# tractor_v2.net
KiCad netlist of a schematic drawn in EAGLE
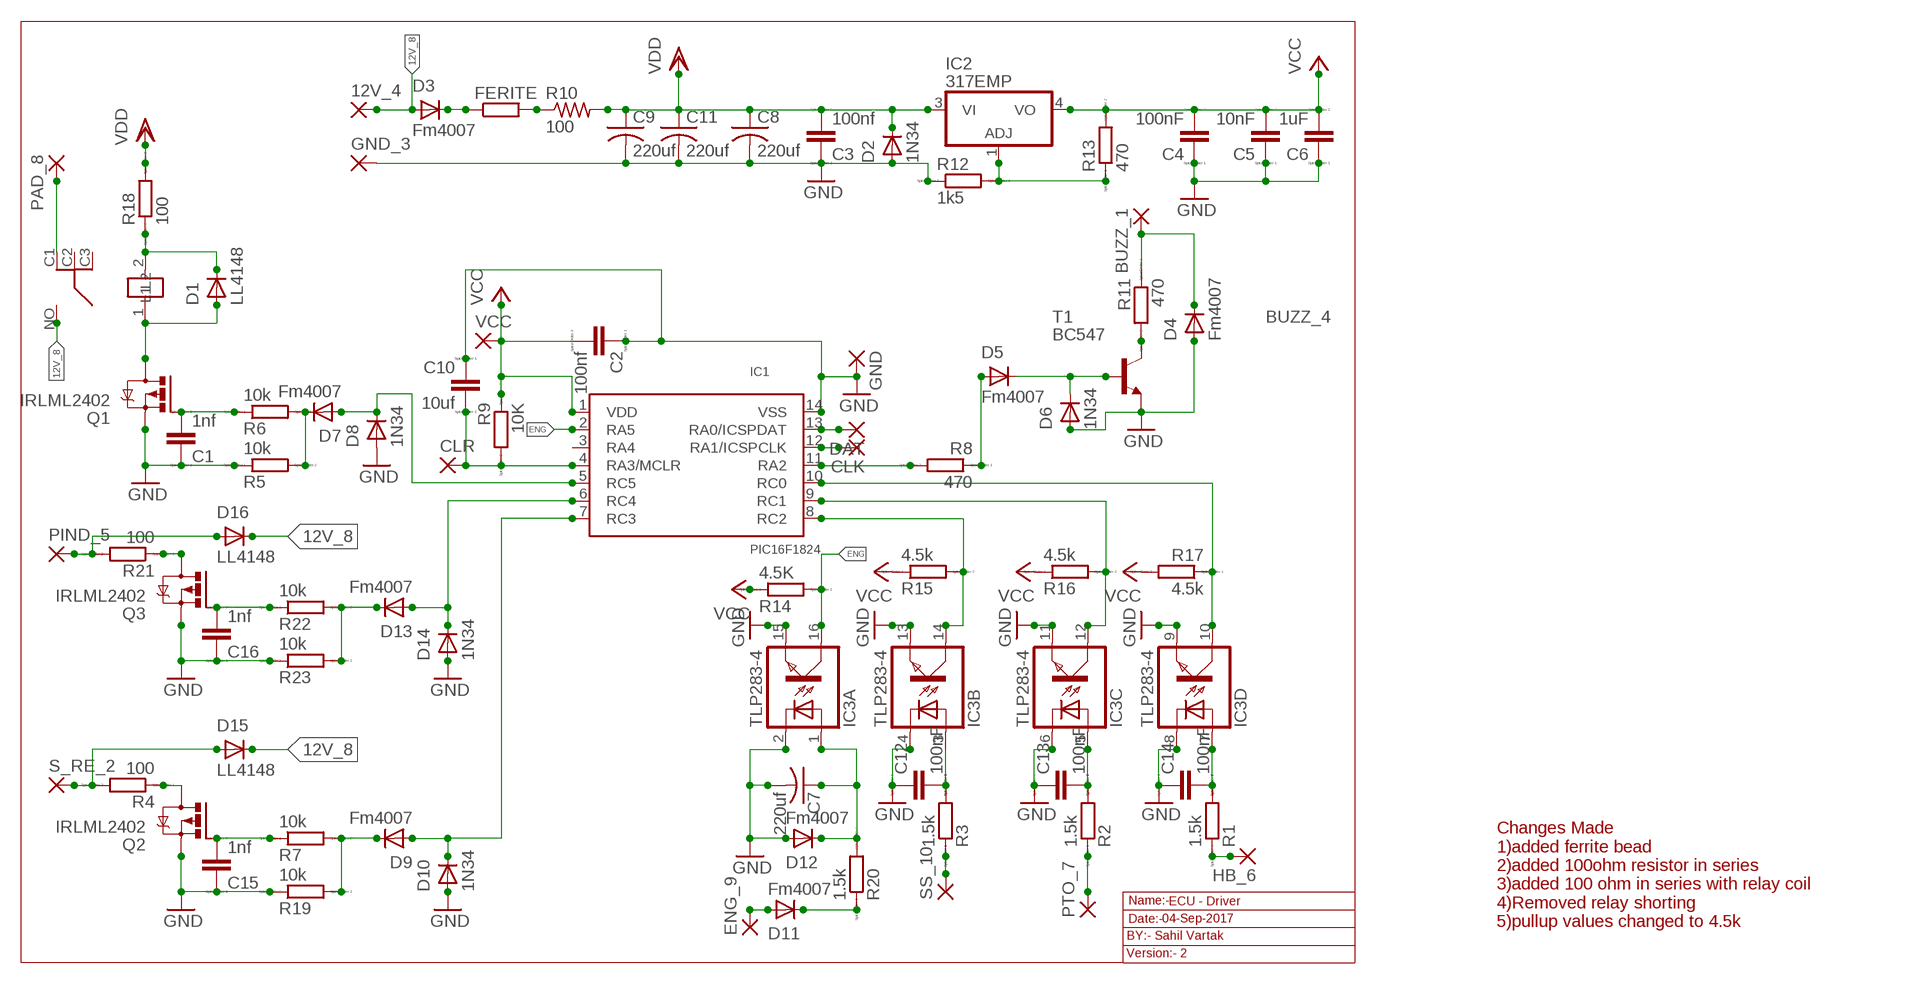
[diagram p0: schematic, sheet 1]

(export (version "E")
  (design (tool "Eeschema 10.0.6"))
  (components
    (comp (ref "12V_4")
      (value "2,54/1,1")
      (footprint "eagle-import:2,54_1,1")
      (libsource (lib "eagle-import") (part "2,54/1,1"))
    )
    (comp (ref "BUZZ_1")
      (value "2,54/1,1")
      (footprint "eagle-import:2,54_1,1")
      (libsource (lib "eagle-import") (part "2,54/1,1"))
    )
    (comp (ref "C1")
      (value "1nf")
      (footprint "eagle-import:C0603")
      (libsource (lib "eagle-import") (part "CC0603"))
    )
    (comp (ref "C2")
      (value "100nf")
      (footprint "eagle-import:C0603")
      (libsource (lib "eagle-import") (part "CC0603"))
    )
    (comp (ref "C3")
      (value "100nf")
      (footprint "eagle-import:C0603")
      (libsource (lib "eagle-import") (part "CC0603"))
    )
    (comp (ref "C4")
      (value "100nF")
      (footprint "eagle-import:C0603")
      (libsource (lib "eagle-import") (part "CC0603"))
    )
    (comp (ref "C5")
      (value "10nF")
      (footprint "eagle-import:C0603")
      (libsource (lib "eagle-import") (part "CC0603"))
    )
    (comp (ref "C6")
      (value "1uF")
      (footprint "eagle-import:C0603")
      (libsource (lib "eagle-import") (part "CC0603"))
    )
    (comp (ref "C7")
      (value "220uf")
      (footprint "eagle-import:C025-025X050")
      (libsource (lib "eagle-import") (part "C-US025-025X050"))
    )
    (comp (ref "C8")
      (value "220uf")
      (footprint "eagle-import:C025-025X050")
      (libsource (lib "eagle-import") (part "C-US025-025X050"))
    )
    (comp (ref "C9")
      (value "220uf")
      (footprint "eagle-import:C025-025X050")
      (libsource (lib "eagle-import") (part "C-US025-025X050"))
    )
    (comp (ref "C10")
      (value "10uf")
      (footprint "eagle-import:C0603")
      (libsource (lib "eagle-import") (part "CC0603"))
    )
    (comp (ref "C11")
      (value "220uf")
      (footprint "eagle-import:C025-025X050")
      (libsource (lib "eagle-import") (part "C-US025-025X050"))
    )
    (comp (ref "C12")
      (value "100nF")
      (footprint "eagle-import:C0603")
      (libsource (lib "eagle-import") (part "CC0603"))
    )
    (comp (ref "C13")
      (value "100nF")
      (footprint "eagle-import:C0603")
      (libsource (lib "eagle-import") (part "CC0603"))
    )
    (comp (ref "C14")
      (value "100nF")
      (footprint "eagle-import:C0603")
      (libsource (lib "eagle-import") (part "CC0603"))
    )
    (comp (ref "C15")
      (value "1nf")
      (footprint "eagle-import:C0603")
      (libsource (lib "eagle-import") (part "CC0603"))
    )
    (comp (ref "C16")
      (value "1nf")
      (footprint "eagle-import:C0603")
      (libsource (lib "eagle-import") (part "CC0603"))
    )
    (comp (ref "CLK")
      (value "1,6/0,8")
      (footprint "eagle-import:1,6_0,8")
      (libsource (lib "eagle-import") (part "1,6/0,8"))
    )
    (comp (ref "CLR")
      (value "1,6/0,8")
      (footprint "eagle-import:1,6_0,8")
      (libsource (lib "eagle-import") (part "1,6/0,8"))
    )
    (comp (ref "D1")
      (value "LL4148")
      (footprint "eagle-import:SMA-DO214AC")
      (libsource (lib "eagle-import") (part "GF1"))
    )
    (comp (ref "D2")
      (value "1N34")
      (footprint "eagle-import:SMA-DO214AC")
      (libsource (lib "eagle-import") (part "GF1"))
    )
    (comp (ref "D3")
      (value "Fm4007")
      (footprint "eagle-import:SMA-DO214AC")
      (libsource (lib "eagle-import") (part "GF1"))
    )
    (comp (ref "D4")
      (value "Fm4007")
      (footprint "eagle-import:SMA-DO214AC")
      (libsource (lib "eagle-import") (part "GF1"))
    )
    (comp (ref "D5")
      (value "Fm4007")
      (footprint "eagle-import:SMA-DO214AC")
      (libsource (lib "eagle-import") (part "GF1"))
    )
    (comp (ref "D6")
      (value "1N34")
      (footprint "eagle-import:SMA-DO214AC")
      (libsource (lib "eagle-import") (part "GF1"))
    )
    (comp (ref "D7")
      (value "Fm4007")
      (footprint "eagle-import:SMA-DO214AC")
      (libsource (lib "eagle-import") (part "GF1"))
    )
    (comp (ref "D8")
      (value "1N34")
      (footprint "eagle-import:SMA-DO214AC")
      (libsource (lib "eagle-import") (part "GF1"))
    )
    (comp (ref "D9")
      (value "Fm4007")
      (footprint "eagle-import:SMA-DO214AC")
      (libsource (lib "eagle-import") (part "GF1"))
    )
    (comp (ref "D10")
      (value "1N34")
      (footprint "eagle-import:SMA-DO214AC")
      (libsource (lib "eagle-import") (part "GF1"))
    )
    (comp (ref "D11")
      (value "Fm4007")
      (footprint "eagle-import:SMA-DO214AC")
      (libsource (lib "eagle-import") (part "GF1"))
    )
    (comp (ref "D12")
      (value "Fm4007")
      (footprint "eagle-import:SMA-DO214AC")
      (libsource (lib "eagle-import") (part "GF1"))
    )
    (comp (ref "D13")
      (value "Fm4007")
      (footprint "eagle-import:SMA-DO214AC")
      (libsource (lib "eagle-import") (part "GF1"))
    )
    (comp (ref "D14")
      (value "1N34")
      (footprint "eagle-import:SMA-DO214AC")
      (libsource (lib "eagle-import") (part "GF1"))
    )
    (comp (ref "D15")
      (value "LL4148")
      (footprint "eagle-import:SMA-DO214AC")
      (libsource (lib "eagle-import") (part "GF1"))
    )
    (comp (ref "D16")
      (value "LL4148")
      (footprint "eagle-import:SMA-DO214AC")
      (libsource (lib "eagle-import") (part "GF1"))
    )
    (comp (ref "DAT")
      (value "1,6/0,8")
      (footprint "eagle-import:1,6_0,8")
      (libsource (lib "eagle-import") (part "1,6/0,8"))
    )
    (comp (ref "ENG_9")
      (value "2,54/1,1")
      (footprint "eagle-import:2,54_1,1")
      (libsource (lib "eagle-import") (part "2,54/1,1"))
    )
    (comp (ref "FERITE")
      (value "R-EU_R0603")
      (footprint "eagle-import:R0603")
      (libsource (lib "eagle-import") (part "R-EU_R0603"))
    )
    (comp (ref "GND")
      (value "1,6/0,8")
      (footprint "eagle-import:1,6_0,8")
      (libsource (lib "eagle-import") (part "1,6/0,8"))
    )
    (comp (ref "GND_3")
      (value "2,54/1,1")
      (footprint "eagle-import:2,54_1,1")
      (libsource (lib "eagle-import") (part "2,54/1,1"))
    )
    (comp (ref "HB_6")
      (value "2,54/1,1")
      (footprint "eagle-import:2,54_1,1")
      (libsource (lib "eagle-import") (part "2,54/1,1"))
    )
    (comp (ref "IC1")
      (value "PIC16F1824")
      (footprint "eagle-import:SO-14")
      (libsource (lib "eagle-import") (part "PIC16F1824"))
    )
    (comp (ref "IC2")
      (value "317EMP")
      (footprint "eagle-import:SOT223")
      (libsource (lib "eagle-import") (part "317EMP"))
    )
    (comp (ref "IC3")
      (value "TLP283-4")
      (footprint "eagle-import:MINI-FLAT-16")
      (libsource (lib "eagle-import") (part "TLP283-4"))
    )
    (comp (ref "K2")
      (value "RL703")
      (footprint "eagle-import:RL703")
      (libsource (lib "eagle-import") (part "RL703"))
    )
    (comp (ref "PAD_8")
      (value "2,54/1,1")
      (footprint "eagle-import:2,54_1,1")
      (libsource (lib "eagle-import") (part "2,54/1,1"))
    )
    (comp (ref "PIND_5")
      (value "2,54/1,1")
      (footprint "eagle-import:2,54_1,1")
      (libsource (lib "eagle-import") (part "2,54/1,1"))
    )
    (comp (ref "PTO_7")
      (value "2,54/1,1")
      (footprint "eagle-import:2,54_1,1")
      (libsource (lib "eagle-import") (part "2,54/1,1"))
    )
    (comp (ref "Q1")
      (value "IRLML2402")
      (footprint "eagle-import:MICRO3")
      (libsource (lib "eagle-import") (part "IRLML5203"))
    )
    (comp (ref "Q2")
      (value "IRLML2402")
      (footprint "eagle-import:MICRO3")
      (libsource (lib "eagle-import") (part "IRLML5203"))
    )
    (comp (ref "Q3")
      (value "IRLML2402")
      (footprint "eagle-import:MICRO3")
      (libsource (lib "eagle-import") (part "IRLML5203"))
    )
    (comp (ref "R1")
      (value "1.5k")
      (footprint "eagle-import:R0603")
      (libsource (lib "eagle-import") (part "RR0603"))
    )
    (comp (ref "R2")
      (value "1.5k")
      (footprint "eagle-import:R0603")
      (libsource (lib "eagle-import") (part "RR0603"))
    )
    (comp (ref "R3")
      (value "1.5k")
      (footprint "eagle-import:R0603")
      (libsource (lib "eagle-import") (part "RR0603"))
    )
    (comp (ref "R4")
      (value "100")
      (footprint "eagle-import:R0603")
      (libsource (lib "eagle-import") (part "RR0603"))
    )
    (comp (ref "R5")
      (value "10k")
      (footprint "eagle-import:R0603")
      (libsource (lib "eagle-import") (part "RR0603"))
    )
    (comp (ref "R6")
      (value "10k")
      (footprint "eagle-import:R0603")
      (libsource (lib "eagle-import") (part "RR0603"))
    )
    (comp (ref "R7")
      (value "10k")
      (footprint "eagle-import:R0603")
      (libsource (lib "eagle-import") (part "RR0603"))
    )
    (comp (ref "R8")
      (value "470")
      (footprint "eagle-import:R0603")
      (libsource (lib "eagle-import") (part "RR0603"))
    )
    (comp (ref "R9")
      (value "10K")
      (footprint "eagle-import:R0603")
      (libsource (lib "eagle-import") (part "RR0603"))
    )
    (comp (ref "R10")
      (value "100")
      (footprint "eagle-import:WSC2515")
      (libsource (lib "eagle-import") (part "R-US_WSC2515"))
    )
    (comp (ref "R11")
      (value "470")
      (footprint "eagle-import:R0603")
      (libsource (lib "eagle-import") (part "RR0603"))
    )
    (comp (ref "R12")
      (value "1k5")
      (footprint "eagle-import:R0603")
      (libsource (lib "eagle-import") (part "RR0603"))
    )
    (comp (ref "R13")
      (value "470")
      (footprint "eagle-import:R0603")
      (libsource (lib "eagle-import") (part "RR0603"))
    )
    (comp (ref "R14")
      (value "4.5K")
      (footprint "eagle-import:R0603")
      (libsource (lib "eagle-import") (part "RR0603"))
    )
    (comp (ref "R15")
      (value "4.5k")
      (footprint "eagle-import:R0603")
      (libsource (lib "eagle-import") (part "RR0603"))
    )
    (comp (ref "R16")
      (value "4.5k")
      (footprint "eagle-import:R0603")
      (libsource (lib "eagle-import") (part "RR0603"))
    )
    (comp (ref "R17")
      (value "4.5k")
      (footprint "eagle-import:R0603")
      (libsource (lib "eagle-import") (part "RR0603"))
    )
    (comp (ref "R18")
      (value "100")
      (footprint "eagle-import:R0603")
      (libsource (lib "eagle-import") (part "RR0603"))
    )
    (comp (ref "R19")
      (value "10k")
      (footprint "eagle-import:R0603")
      (libsource (lib "eagle-import") (part "RR0603"))
    )
    (comp (ref "R20")
      (value "1.5k")
      (footprint "eagle-import:R0603")
      (libsource (lib "eagle-import") (part "RR0603"))
    )
    (comp (ref "R21")
      (value "100")
      (footprint "eagle-import:R0603")
      (libsource (lib "eagle-import") (part "RR0603"))
    )
    (comp (ref "R22")
      (value "10k")
      (footprint "eagle-import:R0603")
      (libsource (lib "eagle-import") (part "RR0603"))
    )
    (comp (ref "R23")
      (value "10k")
      (footprint "eagle-import:R0603")
      (libsource (lib "eagle-import") (part "RR0603"))
    )
    (comp (ref "SS_10")
      (value "2,54/1,1")
      (footprint "eagle-import:2,54_1,1")
      (libsource (lib "eagle-import") (part "2,54/1,1"))
    )
    (comp (ref "S_RE_2")
      (value "2,54/1,1")
      (footprint "eagle-import:2,54_1,1")
      (libsource (lib "eagle-import") (part "2,54/1,1"))
    )
    (comp (ref "T1")
      (value "BC547")
      (footprint "eagle-import:TO92")
      (libsource (lib "eagle-import") (part "BC547"))
    )
    (comp (ref "VCC")
      (value "1,6/0,8")
      (footprint "eagle-import:1,6_0,8")
      (libsource (lib "eagle-import") (part "1,6/0,8"))
    )
  )
  (nets
    (net (code "1") (name "/BUZZ_4") (class "Default")
      (node (ref "BUZZ_1") (pin "1") (pinfunction "P_1") (pintype "passive"))
      (node (ref "D4") (pin "K") (pinfunction "C_K") (pintype "passive"))
      (node (ref "R11") (pin "1") (pinfunction "1_1") (pintype "passive"))
    )
    (net (code "2") (name "12V_8") (class "Default")
      (node (ref "12V_4") (pin "1") (pinfunction "P_1") (pintype "passive"))
      (node (ref "D15") (pin "K") (pinfunction "C_K") (pintype "passive"))
      (node (ref "D16") (pin "K") (pinfunction "C_K") (pintype "passive"))
      (node (ref "D3") (pin "A") (pinfunction "A_A") (pintype "passive"))
      (node (ref "K2") (pin "NO") (pinfunction "NO_NO") (pintype "bidirectional"))
    )
    (net (code "3") (name "ENG") (class "Default")
      (node (ref "IC1") (pin "2") (pinfunction "RA5_2") (pintype "bidirectional"))
      (node (ref "IC3") (pin "16") (pinfunction "COL_16") (pintype "passive"))
      (node (ref "R14") (pin "2") (pinfunction "2_2") (pintype "passive"))
    )
    (net (code "4") (name "GND") (class "Default")
      (node (ref "C1") (pin "1") (pinfunction "1_1") (pintype "passive"))
      (node (ref "C10") (pin "1") (pinfunction "1_1") (pintype "passive"))
      (node (ref "C11") (pin "2") (pinfunction "2_2") (pintype "passive"))
      (node (ref "C12") (pin "1") (pinfunction "1_1") (pintype "passive"))
      (node (ref "C13") (pin "1") (pinfunction "1_1") (pintype "passive"))
      (node (ref "C14") (pin "1") (pinfunction "1_1") (pintype "passive"))
      (node (ref "C15") (pin "1") (pinfunction "1_1") (pintype "passive"))
      (node (ref "C16") (pin "1") (pinfunction "1_1") (pintype "passive"))
      (node (ref "C2") (pin "1") (pinfunction "1_1") (pintype "passive"))
      (node (ref "C3") (pin "1") (pinfunction "1_1") (pintype "passive"))
      (node (ref "C4") (pin "1") (pinfunction "1_1") (pintype "passive"))
      (node (ref "C5") (pin "1") (pinfunction "1_1") (pintype "passive"))
      (node (ref "C6") (pin "1") (pinfunction "1_1") (pintype "passive"))
      (node (ref "C7") (pin "2") (pinfunction "2_2") (pintype "passive"))
      (node (ref "C8") (pin "2") (pinfunction "2_2") (pintype "passive"))
      (node (ref "C9") (pin "2") (pinfunction "2_2") (pintype "passive"))
      (node (ref "D10") (pin "A") (pinfunction "A_A") (pintype "passive"))
      (node (ref "D12") (pin "A") (pinfunction "A_A") (pintype "passive"))
      (node (ref "D14") (pin "A") (pinfunction "A_A") (pintype "passive"))
      (node (ref "D2") (pin "A") (pinfunction "A_A") (pintype "passive"))
      (node (ref "D4") (pin "A") (pinfunction "A_A") (pintype "passive"))
      (node (ref "D6") (pin "A") (pinfunction "A_A") (pintype "passive"))
      (node (ref "D8") (pin "A") (pinfunction "A_A") (pintype "passive"))
      (node (ref "GND") (pin "1") (pinfunction "P_1") (pintype "passive"))
      (node (ref "GND_3") (pin "1") (pinfunction "P_1") (pintype "passive"))
      (node (ref "IC1") (pin "14") (pinfunction "VSS_14") (pintype "bidirectional"))
      (node (ref "IC3") (pin "11") (pinfunction "EMIT_11") (pintype "passive"))
      (node (ref "IC3") (pin "13") (pinfunction "EMIT_13") (pintype "passive"))
      (node (ref "IC3") (pin "15") (pinfunction "EMIT_15") (pintype "passive"))
      (node (ref "IC3") (pin "2") (pinfunction "C_2") (pintype "passive"))
      (node (ref "IC3") (pin "4") (pinfunction "C_4") (pintype "passive"))
      (node (ref "IC3") (pin "6") (pinfunction "C_6") (pintype "passive"))
      (node (ref "IC3") (pin "8") (pinfunction "C_8") (pintype "passive"))
      (node (ref "IC3") (pin "9") (pinfunction "EMIT_9") (pintype "passive"))
      (node (ref "Q1") (pin "2") (pinfunction "S_2") (pintype "passive"))
      (node (ref "Q2") (pin "2") (pinfunction "S_2") (pintype "passive"))
      (node (ref "Q3") (pin "2") (pinfunction "S_2") (pintype "passive"))
      (node (ref "R12") (pin "1") (pinfunction "1_1") (pintype "passive"))
      (node (ref "R19") (pin "1") (pinfunction "1_1") (pintype "passive"))
      (node (ref "R23") (pin "1") (pinfunction "1_1") (pintype "passive"))
      (node (ref "R5") (pin "1") (pinfunction "1_1") (pintype "passive"))
      (node (ref "T1") (pin "1") (pinfunction "E_1") (pintype "passive"))
    )
    (net (code "5") (name "Net-(CLK-P)") (class "Default")
      (node (ref "CLK") (pin "1") (pinfunction "P_1") (pintype "passive"))
      (node (ref "IC1") (pin "12") (pinfunction "RA1/ICSPCLK_12") (pintype "bidirectional"))
    )
    (net (code "6") (name "Net-(CLR-P)") (class "Default")
      (node (ref "C10") (pin "2") (pinfunction "2_2") (pintype "passive"))
      (node (ref "CLR") (pin "1") (pinfunction "P_1") (pintype "passive"))
      (node (ref "IC1") (pin "4") (pinfunction "RA3/MCLR_4") (pintype "bidirectional"))
      (node (ref "R9") (pin "2") (pinfunction "2_2") (pintype "passive"))
    )
    (net (code "7") (name "Net-(D1-C)") (class "Default")
      (node (ref "D1") (pin "K") (pinfunction "C_K") (pintype "passive"))
      (node (ref "K2") (pin "2") (pinfunction "L1_2") (pintype "bidirectional"))
      (node (ref "R18") (pin "1") (pinfunction "1_1") (pintype "passive"))
    )
    (net (code "8") (name "Net-(D3-C)") (class "Default")
      (node (ref "D3") (pin "K") (pinfunction "C_K") (pintype "passive"))
      (node (ref "FERITE") (pin "1") (pinfunction "1_1") (pintype "passive"))
    )
    (net (code "9") (name "Net-(D5-C)") (class "Default")
      (node (ref "D5") (pin "K") (pinfunction "C_K") (pintype "passive"))
      (node (ref "D6") (pin "K") (pinfunction "C_K") (pintype "passive"))
      (node (ref "T1") (pin "2") (pinfunction "B_2") (pintype "passive"))
    )
    (net (code "10") (name "Net-(D5-PadA)") (class "Default")
      (node (ref "D5") (pin "A") (pinfunction "A_A") (pintype "passive"))
      (node (ref "R8") (pin "1") (pinfunction "1_1") (pintype "passive"))
    )
    (net (code "11") (name "Net-(D7-C)") (class "Default")
      (node (ref "D7") (pin "K") (pinfunction "C_K") (pintype "passive"))
      (node (ref "R5") (pin "2") (pinfunction "2_2") (pintype "passive"))
      (node (ref "R6") (pin "2") (pinfunction "2_2") (pintype "passive"))
    )
    (net (code "12") (name "Net-(D8-C)") (class "Default")
      (node (ref "D7") (pin "A") (pinfunction "A_A") (pintype "passive"))
      (node (ref "D8") (pin "K") (pinfunction "C_K") (pintype "passive"))
      (node (ref "IC1") (pin "5") (pinfunction "RC5_5") (pintype "bidirectional"))
    )
    (net (code "13") (name "Net-(D9-C)") (class "Default")
      (node (ref "D9") (pin "K") (pinfunction "C_K") (pintype "passive"))
      (node (ref "R19") (pin "2") (pinfunction "2_2") (pintype "passive"))
      (node (ref "R7") (pin "2") (pinfunction "2_2") (pintype "passive"))
    )
    (net (code "14") (name "Net-(D10-C)") (class "Default")
      (node (ref "D10") (pin "K") (pinfunction "C_K") (pintype "passive"))
      (node (ref "D9") (pin "A") (pinfunction "A_A") (pintype "passive"))
      (node (ref "IC1") (pin "7") (pinfunction "RC3_7") (pintype "bidirectional"))
    )
    (net (code "15") (name "Net-(D11-C)") (class "Default")
      (node (ref "D11") (pin "K") (pinfunction "C_K") (pintype "passive"))
      (node (ref "R20") (pin "1") (pinfunction "1_1") (pintype "passive"))
    )
    (net (code "16") (name "Net-(D12-C)") (class "Default")
      (node (ref "C7") (pin "1") (pinfunction "1_1") (pintype "passive"))
      (node (ref "D12") (pin "K") (pinfunction "C_K") (pintype "passive"))
      (node (ref "IC3") (pin "1") (pinfunction "A_1") (pintype "passive"))
      (node (ref "R20") (pin "2") (pinfunction "2_2") (pintype "passive"))
    )
    (net (code "17") (name "Net-(D13-C)") (class "Default")
      (node (ref "D13") (pin "K") (pinfunction "C_K") (pintype "passive"))
      (node (ref "R22") (pin "2") (pinfunction "2_2") (pintype "passive"))
      (node (ref "R23") (pin "2") (pinfunction "2_2") (pintype "passive"))
    )
    (net (code "18") (name "Net-(D14-C)") (class "Default")
      (node (ref "D13") (pin "A") (pinfunction "A_A") (pintype "passive"))
      (node (ref "D14") (pin "K") (pinfunction "C_K") (pintype "passive"))
      (node (ref "IC1") (pin "6") (pinfunction "RC4_6") (pintype "bidirectional"))
    )
    (net (code "19") (name "Net-(DAT-P)") (class "Default")
      (node (ref "DAT") (pin "1") (pinfunction "P_1") (pintype "passive"))
      (node (ref "IC1") (pin "13") (pinfunction "RA0/ICSPDAT_13") (pintype "bidirectional"))
    )
    (net (code "20") (name "Net-(ENG_9-P)") (class "Default")
      (node (ref "D11") (pin "A") (pinfunction "A_A") (pintype "passive"))
      (node (ref "ENG_9") (pin "1") (pinfunction "P_1") (pintype "passive"))
    )
    (net (code "21") (name "Net-(FERITE-Pad2)") (class "Default")
      (node (ref "FERITE") (pin "2") (pinfunction "2_2") (pintype "passive"))
      (node (ref "R10") (pin "1") (pinfunction "1_1") (pintype "passive"))
    )
    (net (code "22") (name "Net-(HB_6-P)") (class "Default")
      (node (ref "HB_6") (pin "1") (pinfunction "P_1") (pintype "passive"))
      (node (ref "R1") (pin "1") (pinfunction "1_1") (pintype "passive"))
    )
    (net (code "23") (name "Net-(IC1-RA2)") (class "Default")
      (node (ref "IC1") (pin "11") (pinfunction "RA2_11") (pintype "bidirectional"))
      (node (ref "R8") (pin "2") (pinfunction "2_2") (pintype "passive"))
    )
    (net (code "24") (name "Net-(IC1-RC0)") (class "Default")
      (node (ref "IC1") (pin "10") (pinfunction "RC0_10") (pintype "bidirectional"))
      (node (ref "IC3") (pin "10") (pinfunction "COL_10") (pintype "passive"))
      (node (ref "R17") (pin "1") (pinfunction "1_1") (pintype "passive"))
    )
    (net (code "25") (name "Net-(IC1-RC1)") (class "Default")
      (node (ref "IC1") (pin "9") (pinfunction "RC1_9") (pintype "bidirectional"))
      (node (ref "IC3") (pin "12") (pinfunction "COL_12") (pintype "passive"))
      (node (ref "R16") (pin "2") (pinfunction "2_2") (pintype "passive"))
    )
    (net (code "26") (name "Net-(IC1-RC2)") (class "Default")
      (node (ref "IC1") (pin "8") (pinfunction "RC2_8") (pintype "bidirectional"))
      (node (ref "IC3") (pin "14") (pinfunction "COL_14") (pintype "passive"))
      (node (ref "R15") (pin "2") (pinfunction "2_2") (pintype "passive"))
    )
    (net (code "27") (name "Net-(IC2-ADJ)") (class "Default")
      (node (ref "IC2") (pin "1") (pinfunction "ADJ_1") (pintype "input"))
      (node (ref "R12") (pin "2") (pinfunction "2_2") (pintype "passive"))
      (node (ref "R13") (pin "1") (pinfunction "1_1") (pintype "passive"))
    )
    (net (code "28") (name "Net-(IC3B-A)") (class "Default")
      (node (ref "C12") (pin "2") (pinfunction "2_2") (pintype "passive"))
      (node (ref "IC3") (pin "3") (pinfunction "A_3") (pintype "passive"))
      (node (ref "R3") (pin "2") (pinfunction "2_2") (pintype "passive"))
    )
    (net (code "29") (name "Net-(IC3C-A)") (class "Default")
      (node (ref "C13") (pin "2") (pinfunction "2_2") (pintype "passive"))
      (node (ref "IC3") (pin "5") (pinfunction "A_5") (pintype "passive"))
      (node (ref "R2") (pin "2") (pinfunction "2_2") (pintype "passive"))
    )
    (net (code "30") (name "Net-(IC3D-A)") (class "Default")
      (node (ref "C14") (pin "2") (pinfunction "2_2") (pintype "passive"))
      (node (ref "IC3") (pin "7") (pinfunction "A_7") (pintype "passive"))
      (node (ref "R1") (pin "2") (pinfunction "2_2") (pintype "passive"))
    )
    (net (code "31") (name "Net-(K2-L2)") (class "Default")
      (node (ref "D1") (pin "A") (pinfunction "A_A") (pintype "passive"))
      (node (ref "K2") (pin "1") (pinfunction "L2_1") (pintype "bidirectional"))
      (node (ref "Q1") (pin "3") (pinfunction "D_3") (pintype "passive"))
    )
    (net (code "32") (name "Net-(PAD_8-P)") (class "Default")
      (node (ref "K2") (pin "C1") (pinfunction "C1_C1") (pintype "bidirectional"))
      (node (ref "PAD_8") (pin "1") (pinfunction "P_1") (pintype "passive"))
    )
    (net (code "33") (name "Net-(PIND_5-P)") (class "Default")
      (node (ref "D16") (pin "A") (pinfunction "A_A") (pintype "passive"))
      (node (ref "PIND_5") (pin "1") (pinfunction "P_1") (pintype "passive"))
      (node (ref "R21") (pin "2") (pinfunction "2_2") (pintype "passive"))
    )
    (net (code "34") (name "Net-(PTO_7-P)") (class "Default")
      (node (ref "PTO_7") (pin "1") (pinfunction "P_1") (pintype "passive"))
      (node (ref "R2") (pin "1") (pinfunction "1_1") (pintype "passive"))
    )
    (net (code "35") (name "Net-(Q1-G)") (class "Default")
      (node (ref "C1") (pin "2") (pinfunction "2_2") (pintype "passive"))
      (node (ref "Q1") (pin "1") (pinfunction "G_1") (pintype "passive"))
      (node (ref "R6") (pin "1") (pinfunction "1_1") (pintype "passive"))
    )
    (net (code "36") (name "Net-(Q2-D)") (class "Default")
      (node (ref "Q2") (pin "3") (pinfunction "D_3") (pintype "passive"))
      (node (ref "R4") (pin "1") (pinfunction "1_1") (pintype "passive"))
    )
    (net (code "37") (name "Net-(Q2-G)") (class "Default")
      (node (ref "C15") (pin "2") (pinfunction "2_2") (pintype "passive"))
      (node (ref "Q2") (pin "1") (pinfunction "G_1") (pintype "passive"))
      (node (ref "R7") (pin "1") (pinfunction "1_1") (pintype "passive"))
    )
    (net (code "38") (name "Net-(Q3-D)") (class "Default")
      (node (ref "Q3") (pin "3") (pinfunction "D_3") (pintype "passive"))
      (node (ref "R21") (pin "1") (pinfunction "1_1") (pintype "passive"))
    )
    (net (code "39") (name "Net-(Q3-G)") (class "Default")
      (node (ref "C16") (pin "2") (pinfunction "2_2") (pintype "passive"))
      (node (ref "Q3") (pin "1") (pinfunction "G_1") (pintype "passive"))
      (node (ref "R22") (pin "1") (pinfunction "1_1") (pintype "passive"))
    )
    (net (code "40") (name "Net-(SS_10-P)") (class "Default")
      (node (ref "R3") (pin "1") (pinfunction "1_1") (pintype "passive"))
      (node (ref "SS_10") (pin "1") (pinfunction "P_1") (pintype "passive"))
    )
    (net (code "41") (name "Net-(S_RE_2-P)") (class "Default")
      (node (ref "D15") (pin "A") (pinfunction "A_A") (pintype "passive"))
      (node (ref "R4") (pin "2") (pinfunction "2_2") (pintype "passive"))
      (node (ref "S_RE_2") (pin "1") (pinfunction "P_1") (pintype "passive"))
    )
    (net (code "42") (name "Net-(T1-C)") (class "Default")
      (node (ref "R11") (pin "2") (pinfunction "2_2") (pintype "passive"))
      (node (ref "T1") (pin "3") (pinfunction "C_3") (pintype "passive"))
    )
    (net (code "43") (name "VCC") (class "Default")
      (node (ref "C2") (pin "2") (pinfunction "2_2") (pintype "passive"))
      (node (ref "C4") (pin "2") (pinfunction "2_2") (pintype "passive"))
      (node (ref "C5") (pin "2") (pinfunction "2_2") (pintype "passive"))
      (node (ref "C6") (pin "2") (pinfunction "2_2") (pintype "passive"))
      (node (ref "IC1") (pin "1") (pinfunction "VDD_1") (pintype "bidirectional"))
      (node (ref "IC2") (pin "4") (pinfunction "VO_4") (pintype "passive"))
      (node (ref "R13") (pin "2") (pinfunction "2_2") (pintype "passive"))
      (node (ref "R14") (pin "1") (pinfunction "1_1") (pintype "passive"))
      (node (ref "R15") (pin "1") (pinfunction "1_1") (pintype "passive"))
      (node (ref "R16") (pin "1") (pinfunction "1_1") (pintype "passive"))
      (node (ref "R17") (pin "2") (pinfunction "2_2") (pintype "passive"))
      (node (ref "R9") (pin "1") (pinfunction "1_1") (pintype "passive"))
      (node (ref "VCC") (pin "1") (pinfunction "P_1") (pintype "passive"))
    )
    (net (code "44") (name "VDD") (class "Default")
      (node (ref "C11") (pin "1") (pinfunction "1_1") (pintype "passive"))
      (node (ref "C3") (pin "2") (pinfunction "2_2") (pintype "passive"))
      (node (ref "C8") (pin "1") (pinfunction "1_1") (pintype "passive"))
      (node (ref "C9") (pin "1") (pinfunction "1_1") (pintype "passive"))
      (node (ref "D2") (pin "K") (pinfunction "C_K") (pintype "passive"))
      (node (ref "IC2") (pin "3") (pinfunction "VI_3") (pintype "input"))
      (node (ref "R10") (pin "2") (pinfunction "2_2") (pintype "passive"))
      (node (ref "R18") (pin "2") (pinfunction "2_2") (pintype "passive"))
    )
    (net (code "45") (name "unconnected-(IC1-RA4-Pad3)") (class "Default")
      (node (ref "IC1") (pin "3") (pinfunction "RA4_3") (pintype "bidirectional"))
    )
    (net (code "46") (name "unconnected-(K2-PadC2)") (class "Default")
      (node (ref "K2") (pin "C2") (pinfunction "C2_C2") (pintype "bidirectional"))
    )
    (net (code "47") (name "unconnected-(K2-PadC3)") (class "Default")
      (node (ref "K2") (pin "C3") (pinfunction "C3_C3") (pintype "bidirectional"))
    )
  )
)
